# owl.net
KiCad netlist of a schematic drawn in EAGLE
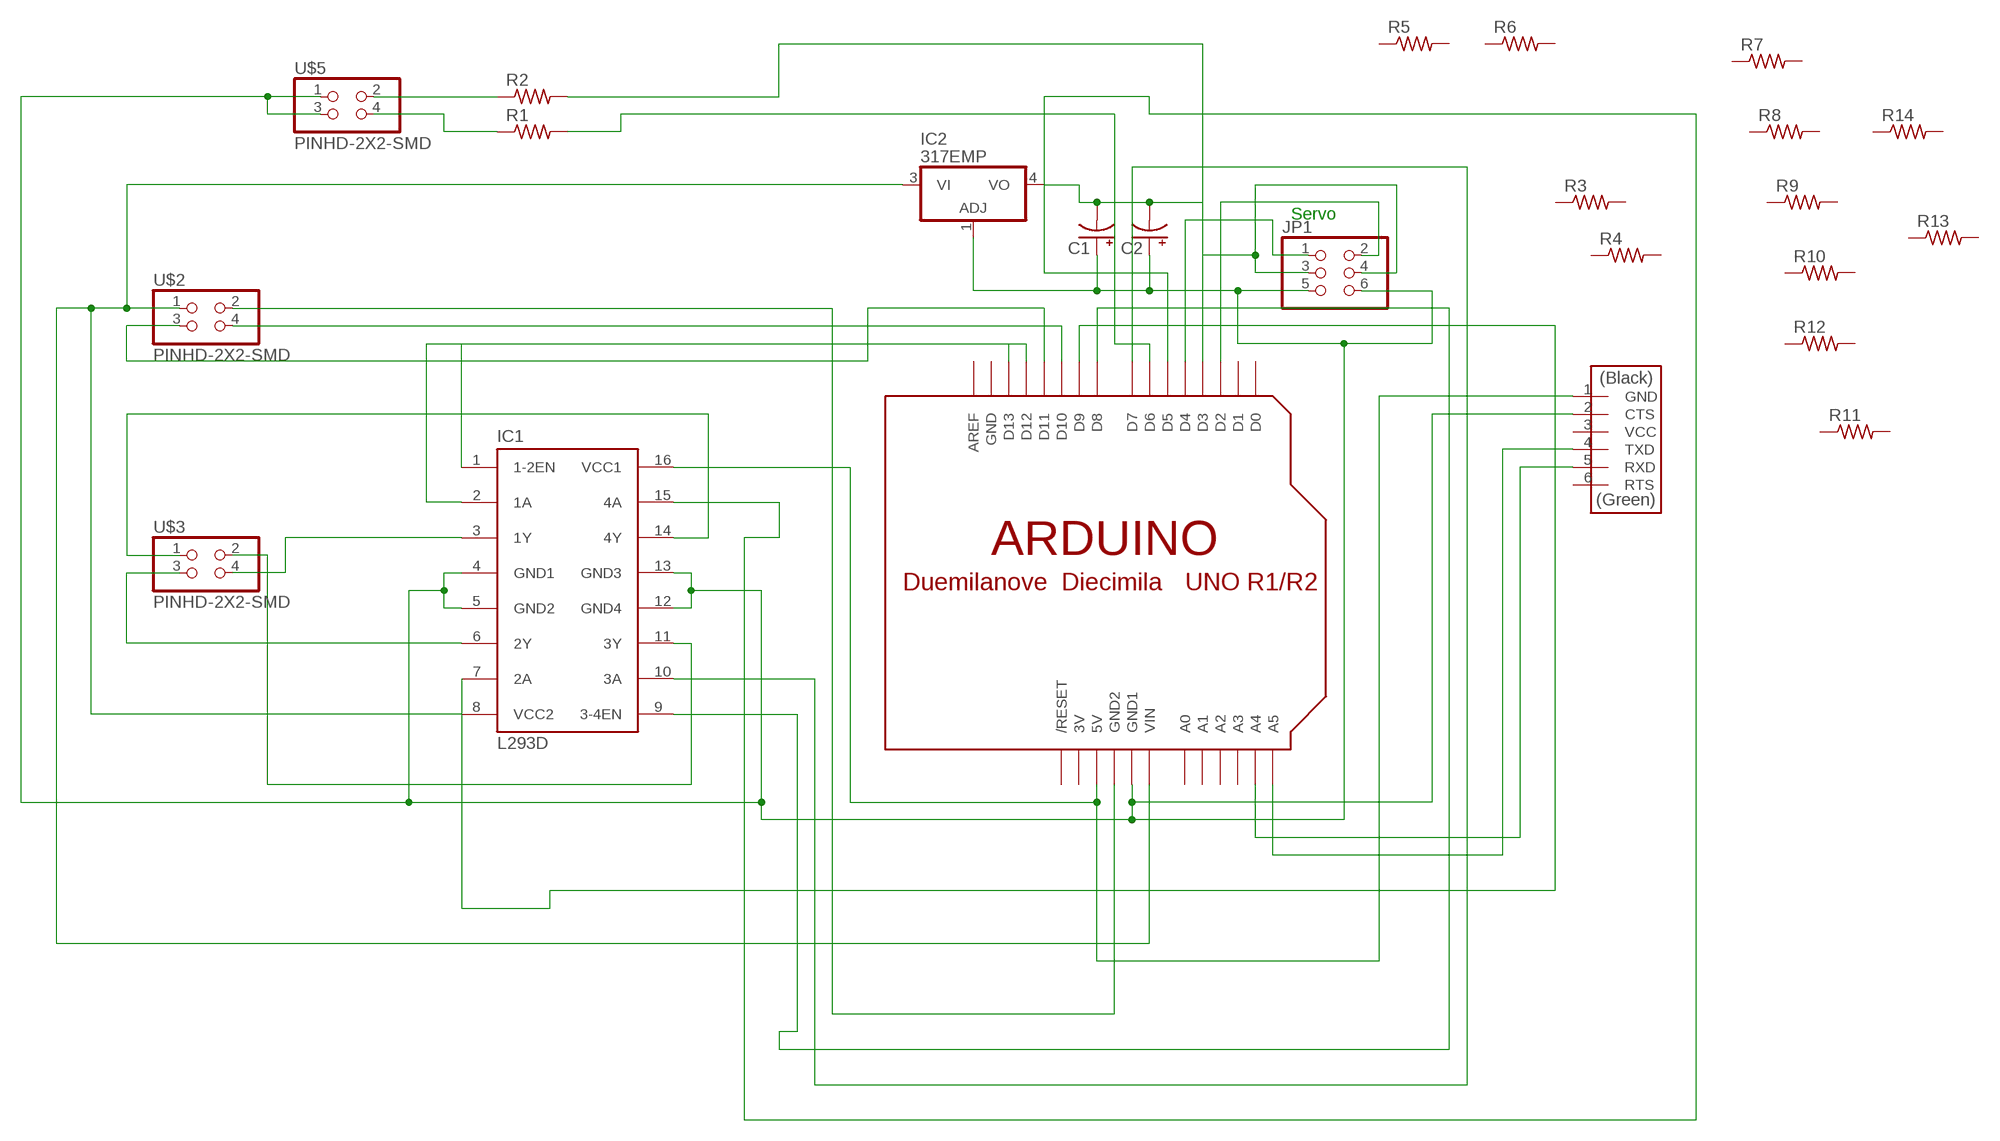
[diagram p0: schematic, sheet 1]

(export (version "E")
  (design (tool "Eeschema 10.0.6"))
  (components
    (comp (ref "C1")
      (value "CPOL-US085CS-1AR")
      (footprint "eagle-import:085CS_1AR")
      (libsource (lib "eagle-import") (part "CPOL-US085CS-1AR"))
    )
    (comp (ref "C2")
      (value "CPOL-US085CS-1AR")
      (footprint "eagle-import:085CS_1AR")
      (libsource (lib "eagle-import") (part "CPOL-US085CS-1AR"))
    )
    (comp (ref "IC1")
      (value "L293D")
      (footprint "eagle-import:DIL16")
      (libsource (lib "eagle-import") (part "L293D"))
    )
    (comp (ref "IC2")
      (value "317EMP")
      (footprint "eagle-import:SOT223")
      (libsource (lib "eagle-import") (part "317EMP"))
    )
    (comp (ref "JP1")
      (value "PINHD-2X3-SMD")
      (footprint "eagle-import:2X03SMD")
      (libsource (lib "eagle-import") (part "PINHD-2X3-SMD"))
    )
    (comp (ref "R1")
      (value "RES-US1206FAB")
      (footprint "eagle-import:R1206FAB")
      (libsource (lib "eagle-import") (part "RES-US1206FAB"))
    )
    (comp (ref "R2")
      (value "RES-US1206FAB")
      (footprint "eagle-import:R1206FAB")
      (libsource (lib "eagle-import") (part "RES-US1206FAB"))
    )
    (comp (ref "R3")
      (value "RES-US1206FAB")
      (footprint "eagle-import:R1206FAB")
      (libsource (lib "eagle-import") (part "RES-US1206FAB"))
    )
    (comp (ref "R4")
      (value "RES-US1206FAB")
      (footprint "eagle-import:R1206FAB")
      (libsource (lib "eagle-import") (part "RES-US1206FAB"))
    )
    (comp (ref "R5")
      (value "RES-US1206FAB")
      (footprint "eagle-import:R1206FAB")
      (libsource (lib "eagle-import") (part "RES-US1206FAB"))
    )
    (comp (ref "R6")
      (value "RES-US1206FAB")
      (footprint "eagle-import:R1206FAB")
      (libsource (lib "eagle-import") (part "RES-US1206FAB"))
    )
    (comp (ref "R7")
      (value "RES-US1206FAB")
      (footprint "eagle-import:R1206FAB")
      (libsource (lib "eagle-import") (part "RES-US1206FAB"))
    )
    (comp (ref "R8")
      (value "RES-US1206FAB")
      (footprint "eagle-import:R1206FAB")
      (libsource (lib "eagle-import") (part "RES-US1206FAB"))
    )
    (comp (ref "R9")
      (value "RES-US1206FAB")
      (footprint "eagle-import:R1206FAB")
      (libsource (lib "eagle-import") (part "RES-US1206FAB"))
    )
    (comp (ref "R10")
      (value "RES-US1206FAB")
      (footprint "eagle-import:R1206FAB")
      (libsource (lib "eagle-import") (part "RES-US1206FAB"))
    )
    (comp (ref "R11")
      (value "RES-US1206FAB")
      (footprint "eagle-import:R1206FAB")
      (libsource (lib "eagle-import") (part "RES-US1206FAB"))
    )
    (comp (ref "R12")
      (value "RES-US1206FAB")
      (footprint "eagle-import:R1206FAB")
      (libsource (lib "eagle-import") (part "RES-US1206FAB"))
    )
    (comp (ref "R13")
      (value "RES-US1206FAB")
      (footprint "eagle-import:R1206FAB")
      (libsource (lib "eagle-import") (part "RES-US1206FAB"))
    )
    (comp (ref "R14")
      (value "RES-US1206FAB")
      (footprint "eagle-import:R1206FAB")
      (libsource (lib "eagle-import") (part "RES-US1206FAB"))
    )
    (comp (ref "U$1")
      (value "ARDUINO-NOHOLE")
      (footprint "eagle-import:ARDUINO-NOHOLE")
      (libsource (lib "eagle-import") (part "ARDUINO-NOHOLE"))
    )
    (comp (ref "U$2")
      (value "PINHD-2X2-SMD")
      (footprint "eagle-import:2X02SMD")
      (libsource (lib "eagle-import") (part "PINHD-2X2-SMD"))
    )
    (comp (ref "U$3")
      (value "PINHD-2X2-SMD")
      (footprint "eagle-import:2X02SMD")
      (libsource (lib "eagle-import") (part "PINHD-2X2-SMD"))
    )
    (comp (ref "U$4")
      (value "FTDI-SMD-HEADER")
      (footprint "eagle-import:1X06SMD")
      (libsource (lib "eagle-import") (part "FTDI-SMD-HEADER"))
    )
    (comp (ref "U$5")
      (value "PINHD-2X2-SMD")
      (footprint "eagle-import:2X02SMD")
      (libsource (lib "eagle-import") (part "PINHD-2X2-SMD"))
    )
  )
  (nets
    (net (code "1") (name "/3V") (class "Default")
      (node (ref "U$1") (pin "3V") (pinfunction "3V_3V") (pintype "power_in"))
    )
    (net (code "2") (name "/GND") (class "Default")
      (node (ref "U$1") (pin "GND") (pinfunction "GND_GND") (pintype "power_in"))
    )
    (net (code "3") (name "Net-(IC1-1-2EN)") (class "Default")
      (node (ref "IC1") (pin "1") (pinfunction "1-2EN_1") (pintype "input"))
      (node (ref "U$1") (pin "D13") (pinfunction "D13_D13") (pintype "bidirectional"))
    )
    (net (code "4") (name "Net-(IC1-1A)") (class "Default")
      (node (ref "IC1") (pin "2") (pinfunction "1A_2") (pintype "input"))
      (node (ref "U$1") (pin "D12") (pinfunction "D12_D12") (pintype "bidirectional"))
    )
    (net (code "5") (name "Net-(IC1-1Y)") (class "Default")
      (node (ref "IC1") (pin "3") (pinfunction "1Y_3") (pintype "output"))
      (node (ref "U$3") (pin "4") (pinfunction "4_4") (pintype "passive"))
    )
    (net (code "6") (name "Net-(IC1-2A)") (class "Default")
      (node (ref "IC1") (pin "7") (pinfunction "2A_7") (pintype "input"))
      (node (ref "U$1") (pin "D9") (pinfunction "D9_D9") (pintype "bidirectional"))
    )
    (net (code "7") (name "Net-(IC1-2Y)") (class "Default")
      (node (ref "IC1") (pin "6") (pinfunction "2Y_6") (pintype "output"))
      (node (ref "U$3") (pin "3") (pinfunction "3_3") (pintype "passive"))
    )
    (net (code "8") (name "Net-(IC1-3-4EN)") (class "Default")
      (node (ref "IC1") (pin "9") (pinfunction "3-4EN_9") (pintype "input"))
      (node (ref "U$1") (pin "D8") (pinfunction "D8_D8") (pintype "bidirectional"))
    )
    (net (code "9") (name "Net-(IC1-3A)") (class "Default")
      (node (ref "IC1") (pin "10") (pinfunction "3A_10") (pintype "input"))
      (node (ref "U$1") (pin "D7") (pinfunction "D7_D7") (pintype "bidirectional"))
    )
    (net (code "10") (name "Net-(IC1-3Y)") (class "Default")
      (node (ref "IC1") (pin "11") (pinfunction "3Y_11") (pintype "output"))
      (node (ref "U$3") (pin "2") (pinfunction "2_2") (pintype "passive"))
    )
    (net (code "11") (name "Net-(IC1-4A)") (class "Default")
      (node (ref "IC1") (pin "15") (pinfunction "4A_15") (pintype "input"))
      (node (ref "U$1") (pin "D5") (pinfunction "D5_D5") (pintype "bidirectional"))
    )
    (net (code "12") (name "Net-(IC1-4Y)") (class "Default")
      (node (ref "IC1") (pin "14") (pinfunction "4Y_14") (pintype "output"))
      (node (ref "U$3") (pin "1") (pinfunction "1_1") (pintype "passive"))
    )
    (net (code "13") (name "Net-(IC1-GND1)") (class "Default")
      (node (ref "C1") (pin "+") (pinfunction "+_+") (pintype "passive"))
      (node (ref "C2") (pin "+") (pinfunction "+_+") (pintype "passive"))
      (node (ref "IC1") (pin "12") (pinfunction "GND4_12") (pintype "power_in"))
      (node (ref "IC1") (pin "13") (pinfunction "GND3_13") (pintype "power_in"))
      (node (ref "IC1") (pin "4") (pinfunction "GND1_4") (pintype "power_in"))
      (node (ref "IC1") (pin "5") (pinfunction "GND2_5") (pintype "power_in"))
      (node (ref "IC2") (pin "1") (pinfunction "ADJ_1") (pintype "input"))
      (node (ref "JP1") (pin "5") (pinfunction "5_5") (pintype "passive"))
      (node (ref "JP1") (pin "6") (pinfunction "6_6") (pintype "passive"))
      (node (ref "U$1") (pin "GND1") (pinfunction "GND1_GND1") (pintype "power_in"))
      (node (ref "U$4") (pin "2") (pinfunction "CTS_2") (pintype "bidirectional"))
      (node (ref "U$5") (pin "1") (pinfunction "1_1") (pintype "passive"))
      (node (ref "U$5") (pin "3") (pinfunction "3_3") (pintype "passive"))
    )
    (net (code "14") (name "Net-(IC1-VCC1)") (class "Default")
      (node (ref "IC1") (pin "16") (pinfunction "VCC1_16") (pintype "power_in"))
      (node (ref "U$1") (pin "5V") (pinfunction "5V_5V") (pintype "power_in"))
      (node (ref "U$4") (pin "1") (pinfunction "GND_1") (pintype "bidirectional"))
    )
    (net (code "15") (name "Net-(IC1-VCC2)") (class "Default")
      (node (ref "IC1") (pin "8") (pinfunction "VCC2_8") (pintype "power_in"))
      (node (ref "IC2") (pin "3") (pinfunction "VI_3") (pintype "input"))
      (node (ref "U$1") (pin "VIN") (pinfunction "VIN_VIN") (pintype "power_in"))
      (node (ref "U$2") (pin "1") (pinfunction "1_1") (pintype "passive"))
    )
    (net (code "16") (name "Net-(IC2-VO)") (class "Default")
      (node (ref "C1") (pin "-") (pinfunction "-_-") (pintype "passive"))
      (node (ref "C2") (pin "-") (pinfunction "-_-") (pintype "passive"))
      (node (ref "IC2") (pin "4") (pinfunction "VO_4") (pintype "passive"))
      (node (ref "JP1") (pin "3") (pinfunction "3_3") (pintype "passive"))
      (node (ref "JP1") (pin "4") (pinfunction "4_4") (pintype "passive"))
    )
    (net (code "17") (name "Net-(JP1-Pad1)") (class "Default")
      (node (ref "JP1") (pin "1") (pinfunction "1_1") (pintype "passive"))
      (node (ref "U$1") (pin "D4") (pinfunction "D4_D4") (pintype "bidirectional"))
    )
    (net (code "18") (name "Net-(JP1-Pad2)") (class "Default")
      (node (ref "JP1") (pin "2") (pinfunction "2_2") (pintype "passive"))
      (node (ref "U$1") (pin "D2") (pinfunction "D2_D2") (pintype "bidirectional"))
    )
    (net (code "19") (name "Net-(R1-Pad1)") (class "Default")
      (node (ref "R1") (pin "1") (pinfunction "1_1") (pintype "passive"))
      (node (ref "U$5") (pin "4") (pinfunction "4_4") (pintype "passive"))
    )
    (net (code "20") (name "Net-(R1-Pad2)") (class "Default")
      (node (ref "R1") (pin "2") (pinfunction "2_2") (pintype "passive"))
      (node (ref "U$1") (pin "D6") (pinfunction "D6_D6") (pintype "bidirectional"))
    )
    (net (code "21") (name "Net-(R2-Pad1)") (class "Default")
      (node (ref "R2") (pin "1") (pinfunction "1_1") (pintype "passive"))
      (node (ref "U$5") (pin "2") (pinfunction "2_2") (pintype "passive"))
    )
    (net (code "22") (name "Net-(R2-Pad2)") (class "Default")
      (node (ref "R2") (pin "2") (pinfunction "2_2") (pintype "passive"))
      (node (ref "U$1") (pin "D3") (pinfunction "D3_D3") (pintype "bidirectional"))
    )
    (net (code "23") (name "Net-(U$1-PadD10)") (class "Default")
      (node (ref "U$1") (pin "D10") (pinfunction "D10_D10") (pintype "bidirectional"))
      (node (ref "U$2") (pin "4") (pinfunction "4_4") (pintype "passive"))
    )
    (net (code "24") (name "Net-(U$1-PadD11)") (class "Default")
      (node (ref "U$1") (pin "D11") (pinfunction "D11_D11") (pintype "bidirectional"))
      (node (ref "U$2") (pin "3") (pinfunction "3_3") (pintype "passive"))
    )
    (net (code "25") (name "Net-(U$1-PadGND2)") (class "Default")
      (node (ref "U$1") (pin "GND2") (pinfunction "GND2_GND2") (pintype "power_in"))
      (node (ref "U$2") (pin "2") (pinfunction "2_2") (pintype "passive"))
    )
    (net (code "26") (name "Net-(U$4-RXD)") (class "Default")
      (node (ref "U$1") (pin "A4") (pinfunction "A4_A4") (pintype "bidirectional"))
      (node (ref "U$4") (pin "5") (pinfunction "RXD_5") (pintype "bidirectional"))
    )
    (net (code "27") (name "Net-(U$4-TXD)") (class "Default")
      (node (ref "U$1") (pin "A5") (pinfunction "A5_A5") (pintype "bidirectional"))
      (node (ref "U$4") (pin "4") (pinfunction "TXD_4") (pintype "bidirectional"))
    )
    (net (code "28") (name "unconnected-(R3-Pad1)") (class "Default")
      (node (ref "R3") (pin "1") (pinfunction "1_1") (pintype "passive"))
    )
    (net (code "29") (name "unconnected-(R3-Pad2)") (class "Default")
      (node (ref "R3") (pin "2") (pinfunction "2_2") (pintype "passive"))
    )
    (net (code "30") (name "unconnected-(R4-Pad1)") (class "Default")
      (node (ref "R4") (pin "1") (pinfunction "1_1") (pintype "passive"))
    )
    (net (code "31") (name "unconnected-(R4-Pad2)") (class "Default")
      (node (ref "R4") (pin "2") (pinfunction "2_2") (pintype "passive"))
    )
    (net (code "32") (name "unconnected-(R5-Pad1)") (class "Default")
      (node (ref "R5") (pin "1") (pinfunction "1_1") (pintype "passive"))
    )
    (net (code "33") (name "unconnected-(R5-Pad2)") (class "Default")
      (node (ref "R5") (pin "2") (pinfunction "2_2") (pintype "passive"))
    )
    (net (code "34") (name "unconnected-(R6-Pad1)") (class "Default")
      (node (ref "R6") (pin "1") (pinfunction "1_1") (pintype "passive"))
    )
    (net (code "35") (name "unconnected-(R6-Pad2)") (class "Default")
      (node (ref "R6") (pin "2") (pinfunction "2_2") (pintype "passive"))
    )
    (net (code "36") (name "unconnected-(R7-Pad1)") (class "Default")
      (node (ref "R7") (pin "1") (pinfunction "1_1") (pintype "passive"))
    )
    (net (code "37") (name "unconnected-(R7-Pad2)") (class "Default")
      (node (ref "R7") (pin "2") (pinfunction "2_2") (pintype "passive"))
    )
    (net (code "38") (name "unconnected-(R8-Pad1)") (class "Default")
      (node (ref "R8") (pin "1") (pinfunction "1_1") (pintype "passive"))
    )
    (net (code "39") (name "unconnected-(R8-Pad2)") (class "Default")
      (node (ref "R8") (pin "2") (pinfunction "2_2") (pintype "passive"))
    )
    (net (code "40") (name "unconnected-(R9-Pad1)") (class "Default")
      (node (ref "R9") (pin "1") (pinfunction "1_1") (pintype "passive"))
    )
    (net (code "41") (name "unconnected-(R9-Pad2)") (class "Default")
      (node (ref "R9") (pin "2") (pinfunction "2_2") (pintype "passive"))
    )
    (net (code "42") (name "unconnected-(R10-Pad1)") (class "Default")
      (node (ref "R10") (pin "1") (pinfunction "1_1") (pintype "passive"))
    )
    (net (code "43") (name "unconnected-(R10-Pad2)") (class "Default")
      (node (ref "R10") (pin "2") (pinfunction "2_2") (pintype "passive"))
    )
    (net (code "44") (name "unconnected-(R11-Pad1)") (class "Default")
      (node (ref "R11") (pin "1") (pinfunction "1_1") (pintype "passive"))
    )
    (net (code "45") (name "unconnected-(R11-Pad2)") (class "Default")
      (node (ref "R11") (pin "2") (pinfunction "2_2") (pintype "passive"))
    )
    (net (code "46") (name "unconnected-(R12-Pad1)") (class "Default")
      (node (ref "R12") (pin "1") (pinfunction "1_1") (pintype "passive"))
    )
    (net (code "47") (name "unconnected-(R12-Pad2)") (class "Default")
      (node (ref "R12") (pin "2") (pinfunction "2_2") (pintype "passive"))
    )
    (net (code "48") (name "unconnected-(R13-Pad1)") (class "Default")
      (node (ref "R13") (pin "1") (pinfunction "1_1") (pintype "passive"))
    )
    (net (code "49") (name "unconnected-(R13-Pad2)") (class "Default")
      (node (ref "R13") (pin "2") (pinfunction "2_2") (pintype "passive"))
    )
    (net (code "50") (name "unconnected-(R14-Pad1)") (class "Default")
      (node (ref "R14") (pin "1") (pinfunction "1_1") (pintype "passive"))
    )
    (net (code "51") (name "unconnected-(R14-Pad2)") (class "Default")
      (node (ref "R14") (pin "2") (pinfunction "2_2") (pintype "passive"))
    )
    (net (code "52") (name "unconnected-(U$1-PadA0)") (class "Default")
      (node (ref "U$1") (pin "A0") (pinfunction "A0_A0") (pintype "bidirectional"))
    )
    (net (code "53") (name "unconnected-(U$1-PadA1)") (class "Default")
      (node (ref "U$1") (pin "A1") (pinfunction "A1_A1") (pintype "bidirectional"))
    )
    (net (code "54") (name "unconnected-(U$1-PadA2)") (class "Default")
      (node (ref "U$1") (pin "A2") (pinfunction "A2_A2") (pintype "bidirectional"))
    )
    (net (code "55") (name "unconnected-(U$1-PadA3)") (class "Default")
      (node (ref "U$1") (pin "A3") (pinfunction "A3_A3") (pintype "bidirectional"))
    )
    (net (code "56") (name "unconnected-(U$1-PadAREF)") (class "Default")
      (node (ref "U$1") (pin "AREF") (pinfunction "AREF_AREF") (pintype "bidirectional"))
    )
    (net (code "57") (name "unconnected-(U$1-PadD0)") (class "Default")
      (node (ref "U$1") (pin "D0") (pinfunction "D0_D0") (pintype "bidirectional"))
    )
    (net (code "58") (name "unconnected-(U$1-PadD1)") (class "Default")
      (node (ref "U$1") (pin "D1") (pinfunction "D1_D1") (pintype "bidirectional"))
    )
    (net (code "59") (name "unconnected-(U$1-{slash}RESET-PadRESET)") (class "Default")
      (node (ref "U$1") (pin "RESET") (pinfunction "/RESET_RESET") (pintype "bidirectional"))
    )
    (net (code "60") (name "unconnected-(U$4-RTS-Pad6)") (class "Default")
      (node (ref "U$4") (pin "6") (pinfunction "RTS_6") (pintype "bidirectional"))
    )
    (net (code "61") (name "unconnected-(U$4-VCC-Pad3)") (class "Default")
      (node (ref "U$4") (pin "3") (pinfunction "VCC_3") (pintype "bidirectional"))
    )
  )
)
